# thermometer_analog_meter.net
KiCad netlist of a schematic drawn in EAGLE
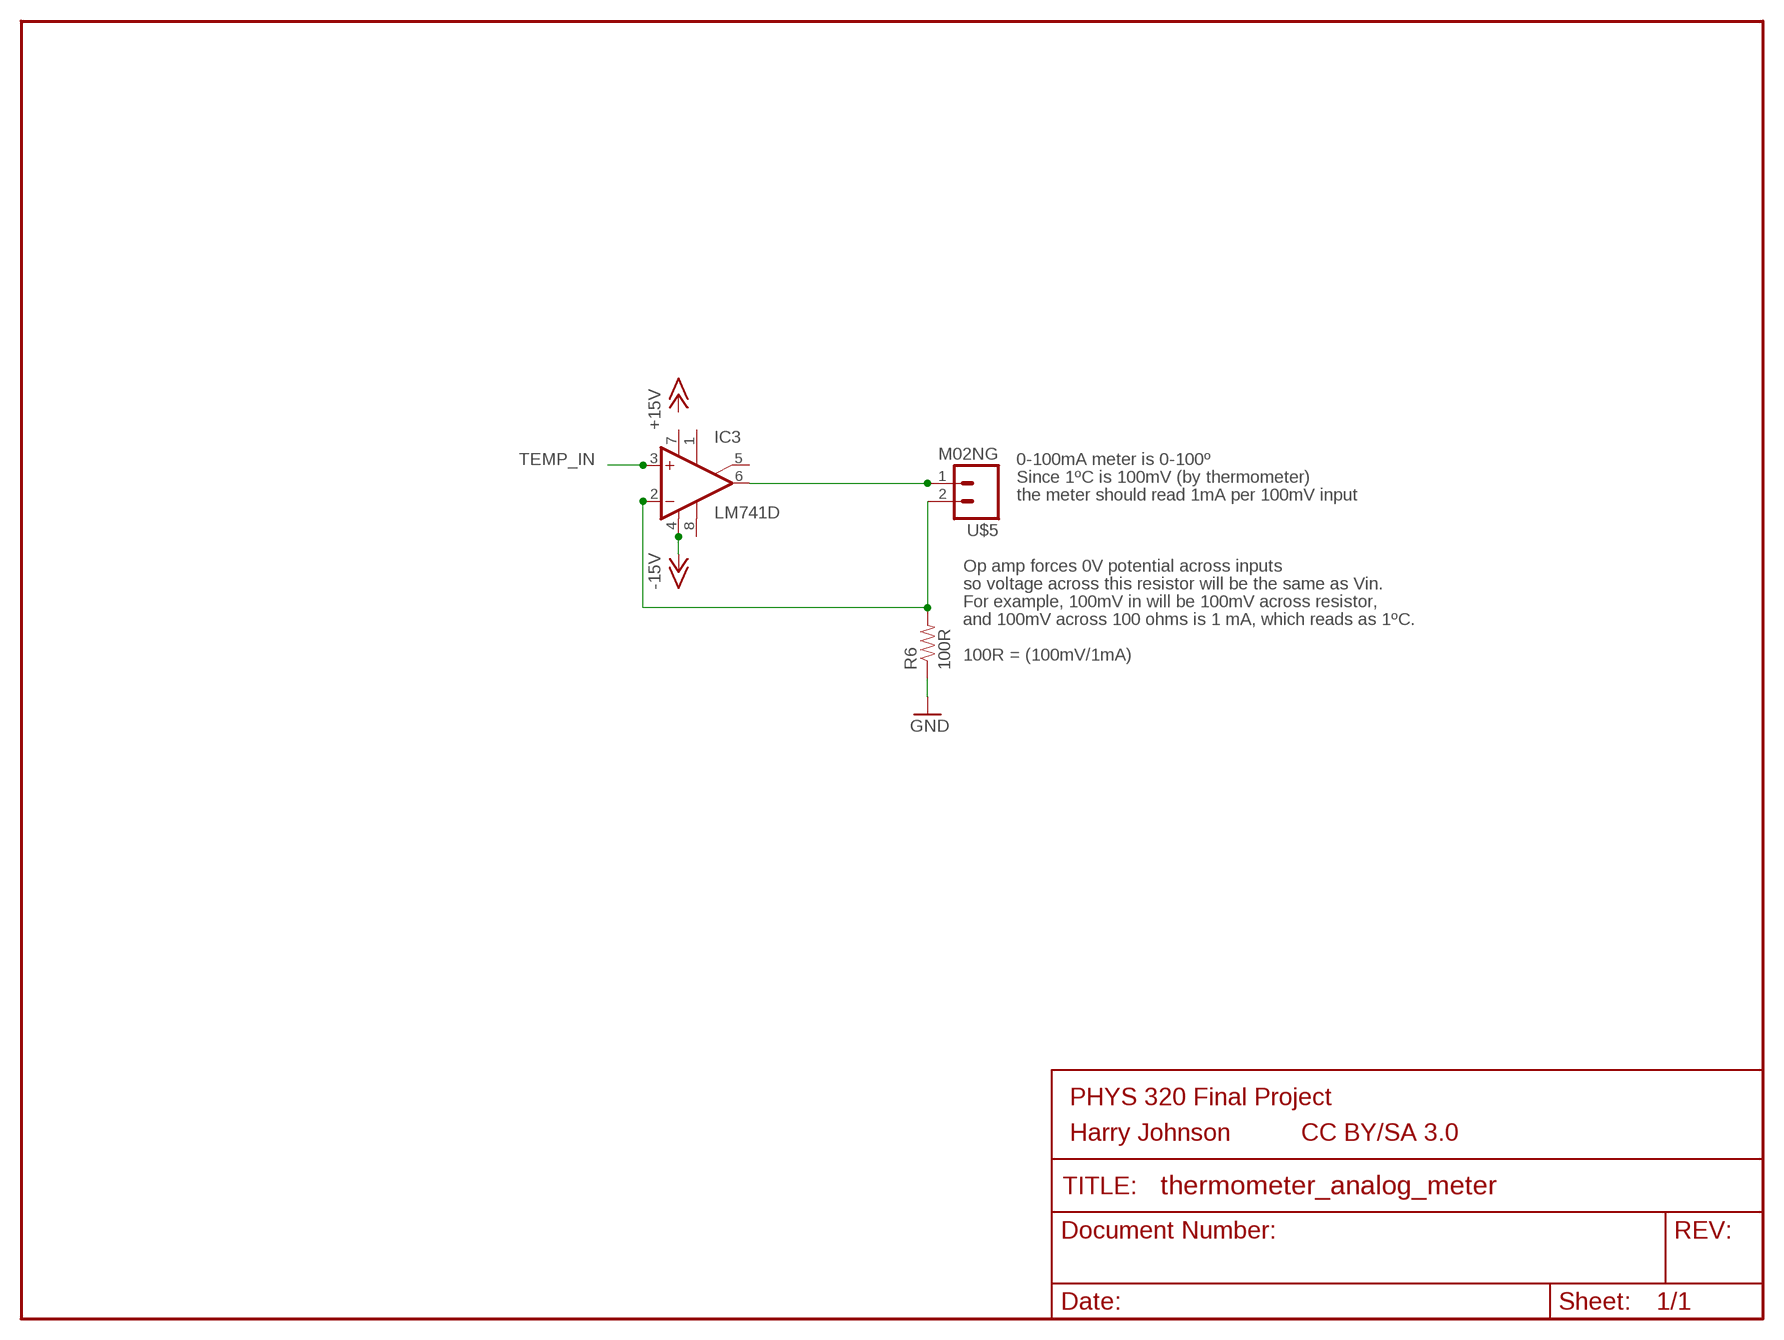
[diagram p0: schematic, sheet 1]

(export (version "E")
  (design (tool "Eeschema 10.0.6"))
  (components
    (comp (ref "IC3")
      (value "LM741D")
      (footprint "eagle-import:SO08")
      (libsource (lib "eagle-import") (part "741DLM"))
    )
    (comp (ref "R6")
      (value "100R")
      (footprint "eagle-import:0805")
      (libsource (lib "eagle-import") (part "RESISTOR"))
    )
    (comp (ref "U$5")
      (value "M02NG")
      (footprint "eagle-import:1X02")
      (libsource (lib "eagle-import") (part "M02NG"))
    )
  )
  (nets
    (net (code "2") (name "-15V") (class "Default")
      (node (ref "IC3") (pin "4") (pinfunction "V-_4") (pintype "power_in"))
    )
    (net (code "3") (name "/TEMP_IN") (class "Default")
      (node (ref "IC3") (pin "3") (pinfunction "+IN_3") (pintype "input"))
    )
    (net (code "4") (name "/V+") (class "Default")
      (node (ref "IC3") (pin "7") (pinfunction "V+_7") (pintype "power_in"))
    )
    (net (code "5") (name "GND") (class "Default")
      (node (ref "R6") (pin "1") (pinfunction "1_1") (pintype "passive"))
    )
    (net (code "6") (name "Net-(IC3--IN)") (class "Default")
      (node (ref "IC3") (pin "2") (pinfunction "-IN_2") (pintype "input"))
      (node (ref "R6") (pin "2") (pinfunction "2_2") (pintype "passive"))
      (node (ref "U$5") (pin "2") (pinfunction "2_2") (pintype "passive"))
    )
    (net (code "7") (name "Net-(IC3-OUT)") (class "Default")
      (node (ref "IC3") (pin "6") (pinfunction "OUT_6") (pintype "output"))
      (node (ref "U$5") (pin "1") (pinfunction "1_1") (pintype "passive"))
    )
    (net (code "8") (name "unconnected-(IC3-ON1-Pad1)") (class "Default")
      (node (ref "IC3") (pin "1") (pinfunction "ON1_1") (pintype "passive"))
    )
    (net (code "9") (name "unconnected-(IC3-ON2-Pad5)") (class "Default")
      (node (ref "IC3") (pin "5") (pinfunction "ON2_5") (pintype "passive"))
    )
    (net (code "10") (name "unconnected-(IC3-OPT-Pad8)") (class "Default")
      (node (ref "IC3") (pin "8") (pinfunction "OPT_8") (pintype "passive"))
    )
  )
)
